# Brakelight2019.net
KiCad netlist of a schematic drawn in EAGLE
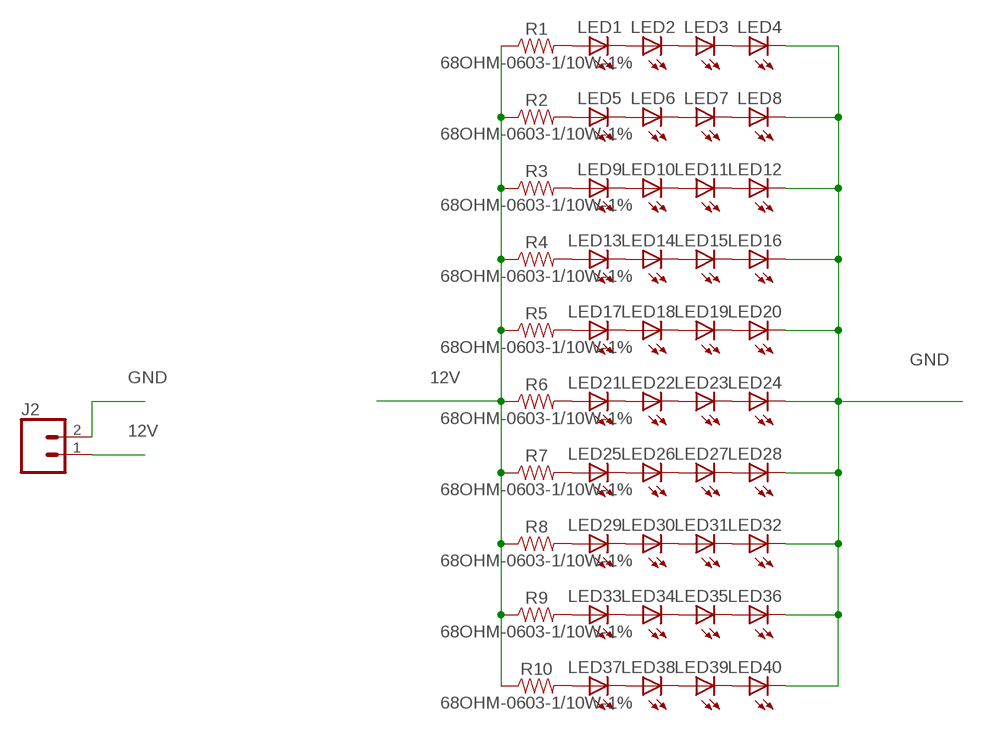
[diagram p0: schematic, sheet 1]

(export (version "E")
  (design (tool "Eeschema 10.0.6"))
  (components
    (comp (ref "J2")
      (value "CONN_02POLAR")
      (footprint "eagle-import:MOLEX-1X2")
      (libsource (lib "eagle-import") (part "CONN_02POLAR"))
    )
    (comp (ref "LED1")
      (value "LED5MM")
      (footprint "eagle-import:LED5MM")
      (libsource (lib "eagle-import") (part "LED5MM"))
    )
    (comp (ref "LED2")
      (value "LED5MM")
      (footprint "eagle-import:LED5MM")
      (libsource (lib "eagle-import") (part "LED5MM"))
    )
    (comp (ref "LED3")
      (value "LED5MM")
      (footprint "eagle-import:LED5MM")
      (libsource (lib "eagle-import") (part "LED5MM"))
    )
    (comp (ref "LED4")
      (value "LED5MM")
      (footprint "eagle-import:LED5MM")
      (libsource (lib "eagle-import") (part "LED5MM"))
    )
    (comp (ref "LED5")
      (value "LED5MM")
      (footprint "eagle-import:LED5MM")
      (libsource (lib "eagle-import") (part "LED5MM"))
    )
    (comp (ref "LED6")
      (value "LED5MM")
      (footprint "eagle-import:LED5MM")
      (libsource (lib "eagle-import") (part "LED5MM"))
    )
    (comp (ref "LED7")
      (value "LED5MM")
      (footprint "eagle-import:LED5MM")
      (libsource (lib "eagle-import") (part "LED5MM"))
    )
    (comp (ref "LED8")
      (value "LED5MM")
      (footprint "eagle-import:LED5MM")
      (libsource (lib "eagle-import") (part "LED5MM"))
    )
    (comp (ref "LED9")
      (value "LED5MM")
      (footprint "eagle-import:LED5MM")
      (libsource (lib "eagle-import") (part "LED5MM"))
    )
    (comp (ref "LED10")
      (value "LED5MM")
      (footprint "eagle-import:LED5MM")
      (libsource (lib "eagle-import") (part "LED5MM"))
    )
    (comp (ref "LED11")
      (value "LED5MM")
      (footprint "eagle-import:LED5MM")
      (libsource (lib "eagle-import") (part "LED5MM"))
    )
    (comp (ref "LED12")
      (value "LED5MM")
      (footprint "eagle-import:LED5MM")
      (libsource (lib "eagle-import") (part "LED5MM"))
    )
    (comp (ref "LED13")
      (value "LED5MM")
      (footprint "eagle-import:LED5MM")
      (libsource (lib "eagle-import") (part "LED5MM"))
    )
    (comp (ref "LED14")
      (value "LED5MM")
      (footprint "eagle-import:LED5MM")
      (libsource (lib "eagle-import") (part "LED5MM"))
    )
    (comp (ref "LED15")
      (value "LED5MM")
      (footprint "eagle-import:LED5MM")
      (libsource (lib "eagle-import") (part "LED5MM"))
    )
    (comp (ref "LED16")
      (value "LED5MM")
      (footprint "eagle-import:LED5MM")
      (libsource (lib "eagle-import") (part "LED5MM"))
    )
    (comp (ref "LED17")
      (value "LED5MM")
      (footprint "eagle-import:LED5MM")
      (libsource (lib "eagle-import") (part "LED5MM"))
    )
    (comp (ref "LED18")
      (value "LED5MM")
      (footprint "eagle-import:LED5MM")
      (libsource (lib "eagle-import") (part "LED5MM"))
    )
    (comp (ref "LED19")
      (value "LED5MM")
      (footprint "eagle-import:LED5MM")
      (libsource (lib "eagle-import") (part "LED5MM"))
    )
    (comp (ref "LED20")
      (value "LED5MM")
      (footprint "eagle-import:LED5MM")
      (libsource (lib "eagle-import") (part "LED5MM"))
    )
    (comp (ref "LED21")
      (value "LED5MM")
      (footprint "eagle-import:LED5MM")
      (libsource (lib "eagle-import") (part "LED5MM"))
    )
    (comp (ref "LED22")
      (value "LED5MM")
      (footprint "eagle-import:LED5MM")
      (libsource (lib "eagle-import") (part "LED5MM"))
    )
    (comp (ref "LED23")
      (value "LED5MM")
      (footprint "eagle-import:LED5MM")
      (libsource (lib "eagle-import") (part "LED5MM"))
    )
    (comp (ref "LED24")
      (value "LED5MM")
      (footprint "eagle-import:LED5MM")
      (libsource (lib "eagle-import") (part "LED5MM"))
    )
    (comp (ref "LED25")
      (value "LED5MM")
      (footprint "eagle-import:LED5MM")
      (libsource (lib "eagle-import") (part "LED5MM"))
    )
    (comp (ref "LED26")
      (value "LED5MM")
      (footprint "eagle-import:LED5MM")
      (libsource (lib "eagle-import") (part "LED5MM"))
    )
    (comp (ref "LED27")
      (value "LED5MM")
      (footprint "eagle-import:LED5MM")
      (libsource (lib "eagle-import") (part "LED5MM"))
    )
    (comp (ref "LED28")
      (value "LED5MM")
      (footprint "eagle-import:LED5MM")
      (libsource (lib "eagle-import") (part "LED5MM"))
    )
    (comp (ref "LED29")
      (value "LED5MM")
      (footprint "eagle-import:LED5MM")
      (libsource (lib "eagle-import") (part "LED5MM"))
    )
    (comp (ref "LED30")
      (value "LED5MM")
      (footprint "eagle-import:LED5MM")
      (libsource (lib "eagle-import") (part "LED5MM"))
    )
    (comp (ref "LED31")
      (value "LED5MM")
      (footprint "eagle-import:LED5MM")
      (libsource (lib "eagle-import") (part "LED5MM"))
    )
    (comp (ref "LED32")
      (value "LED5MM")
      (footprint "eagle-import:LED5MM")
      (libsource (lib "eagle-import") (part "LED5MM"))
    )
    (comp (ref "LED33")
      (value "LED5MM")
      (footprint "eagle-import:LED5MM")
      (libsource (lib "eagle-import") (part "LED5MM"))
    )
    (comp (ref "LED34")
      (value "LED5MM")
      (footprint "eagle-import:LED5MM")
      (libsource (lib "eagle-import") (part "LED5MM"))
    )
    (comp (ref "LED35")
      (value "LED5MM")
      (footprint "eagle-import:LED5MM")
      (libsource (lib "eagle-import") (part "LED5MM"))
    )
    (comp (ref "LED36")
      (value "LED5MM")
      (footprint "eagle-import:LED5MM")
      (libsource (lib "eagle-import") (part "LED5MM"))
    )
    (comp (ref "LED37")
      (value "LED5MM")
      (footprint "eagle-import:LED5MM")
      (libsource (lib "eagle-import") (part "LED5MM"))
    )
    (comp (ref "LED38")
      (value "LED5MM")
      (footprint "eagle-import:LED5MM")
      (libsource (lib "eagle-import") (part "LED5MM"))
    )
    (comp (ref "LED39")
      (value "LED5MM")
      (footprint "eagle-import:LED5MM")
      (libsource (lib "eagle-import") (part "LED5MM"))
    )
    (comp (ref "LED40")
      (value "LED5MM")
      (footprint "eagle-import:LED5MM")
      (libsource (lib "eagle-import") (part "LED5MM"))
    )
    (comp (ref "R1")
      (value "68OHM-0603-1/10W-1%")
      (footprint "eagle-import:0603")
      (libsource (lib "eagle-import") (part "68OHM-0603-1/10W-1%"))
    )
    (comp (ref "R2")
      (value "68OHM-0603-1/10W-1%")
      (footprint "eagle-import:0603")
      (libsource (lib "eagle-import") (part "68OHM-0603-1/10W-1%"))
    )
    (comp (ref "R3")
      (value "68OHM-0603-1/10W-1%")
      (footprint "eagle-import:0603")
      (libsource (lib "eagle-import") (part "68OHM-0603-1/10W-1%"))
    )
    (comp (ref "R4")
      (value "68OHM-0603-1/10W-1%")
      (footprint "eagle-import:0603")
      (libsource (lib "eagle-import") (part "68OHM-0603-1/10W-1%"))
    )
    (comp (ref "R5")
      (value "68OHM-0603-1/10W-1%")
      (footprint "eagle-import:0603")
      (libsource (lib "eagle-import") (part "68OHM-0603-1/10W-1%"))
    )
    (comp (ref "R6")
      (value "68OHM-0603-1/10W-1%")
      (footprint "eagle-import:0603")
      (libsource (lib "eagle-import") (part "68OHM-0603-1/10W-1%"))
    )
    (comp (ref "R7")
      (value "68OHM-0603-1/10W-1%")
      (footprint "eagle-import:0603")
      (libsource (lib "eagle-import") (part "68OHM-0603-1/10W-1%"))
    )
    (comp (ref "R8")
      (value "68OHM-0603-1/10W-1%")
      (footprint "eagle-import:0603")
      (libsource (lib "eagle-import") (part "68OHM-0603-1/10W-1%"))
    )
    (comp (ref "R9")
      (value "68OHM-0603-1/10W-1%")
      (footprint "eagle-import:0603")
      (libsource (lib "eagle-import") (part "68OHM-0603-1/10W-1%"))
    )
    (comp (ref "R10")
      (value "68OHM-0603-1/10W-1%")
      (footprint "eagle-import:0603")
      (libsource (lib "eagle-import") (part "68OHM-0603-1/10W-1%"))
    )
  )
  (nets
    (net (code "1") (name "/12V") (class "Default")
      (node (ref "J2") (pin "1") (pinfunction "1_1") (pintype "passive"))
      (node (ref "R1") (pin "1") (pinfunction "1_1") (pintype "passive"))
      (node (ref "R10") (pin "1") (pinfunction "1_1") (pintype "passive"))
      (node (ref "R2") (pin "1") (pinfunction "1_1") (pintype "passive"))
      (node (ref "R3") (pin "1") (pinfunction "1_1") (pintype "passive"))
      (node (ref "R4") (pin "1") (pinfunction "1_1") (pintype "passive"))
      (node (ref "R5") (pin "1") (pinfunction "1_1") (pintype "passive"))
      (node (ref "R6") (pin "1") (pinfunction "1_1") (pintype "passive"))
      (node (ref "R7") (pin "1") (pinfunction "1_1") (pintype "passive"))
      (node (ref "R8") (pin "1") (pinfunction "1_1") (pintype "passive"))
      (node (ref "R9") (pin "1") (pinfunction "1_1") (pintype "passive"))
    )
    (net (code "2") (name "/GND") (class "Default")
      (node (ref "J2") (pin "2") (pinfunction "2_2") (pintype "passive"))
      (node (ref "LED12") (pin "K") (pinfunction "C_K") (pintype "passive"))
      (node (ref "LED16") (pin "K") (pinfunction "C_K") (pintype "passive"))
      (node (ref "LED20") (pin "K") (pinfunction "C_K") (pintype "passive"))
      (node (ref "LED24") (pin "K") (pinfunction "C_K") (pintype "passive"))
      (node (ref "LED28") (pin "K") (pinfunction "C_K") (pintype "passive"))
      (node (ref "LED32") (pin "K") (pinfunction "C_K") (pintype "passive"))
      (node (ref "LED36") (pin "K") (pinfunction "C_K") (pintype "passive"))
      (node (ref "LED4") (pin "K") (pinfunction "C_K") (pintype "passive"))
      (node (ref "LED40") (pin "K") (pinfunction "C_K") (pintype "passive"))
      (node (ref "LED8") (pin "K") (pinfunction "C_K") (pintype "passive"))
    )
    (net (code "3") (name "Net-(LED1-C)") (class "Default")
      (node (ref "LED1") (pin "K") (pinfunction "C_K") (pintype "passive"))
      (node (ref "LED2") (pin "A") (pinfunction "A_A") (pintype "passive"))
    )
    (net (code "4") (name "Net-(LED1-PadA)") (class "Default")
      (node (ref "LED1") (pin "A") (pinfunction "A_A") (pintype "passive"))
      (node (ref "R1") (pin "2") (pinfunction "2_2") (pintype "passive"))
    )
    (net (code "5") (name "Net-(LED2-C)") (class "Default")
      (node (ref "LED2") (pin "K") (pinfunction "C_K") (pintype "passive"))
      (node (ref "LED3") (pin "A") (pinfunction "A_A") (pintype "passive"))
    )
    (net (code "6") (name "Net-(LED3-C)") (class "Default")
      (node (ref "LED3") (pin "K") (pinfunction "C_K") (pintype "passive"))
      (node (ref "LED4") (pin "A") (pinfunction "A_A") (pintype "passive"))
    )
    (net (code "7") (name "Net-(LED5-C)") (class "Default")
      (node (ref "LED5") (pin "K") (pinfunction "C_K") (pintype "passive"))
      (node (ref "LED6") (pin "A") (pinfunction "A_A") (pintype "passive"))
    )
    (net (code "8") (name "Net-(LED5-PadA)") (class "Default")
      (node (ref "LED5") (pin "A") (pinfunction "A_A") (pintype "passive"))
      (node (ref "R2") (pin "2") (pinfunction "2_2") (pintype "passive"))
    )
    (net (code "9") (name "Net-(LED6-C)") (class "Default")
      (node (ref "LED6") (pin "K") (pinfunction "C_K") (pintype "passive"))
      (node (ref "LED7") (pin "A") (pinfunction "A_A") (pintype "passive"))
    )
    (net (code "10") (name "Net-(LED7-C)") (class "Default")
      (node (ref "LED7") (pin "K") (pinfunction "C_K") (pintype "passive"))
      (node (ref "LED8") (pin "A") (pinfunction "A_A") (pintype "passive"))
    )
    (net (code "11") (name "Net-(LED9-C)") (class "Default")
      (node (ref "LED10") (pin "A") (pinfunction "A_A") (pintype "passive"))
      (node (ref "LED9") (pin "K") (pinfunction "C_K") (pintype "passive"))
    )
    (net (code "12") (name "Net-(LED9-PadA)") (class "Default")
      (node (ref "LED9") (pin "A") (pinfunction "A_A") (pintype "passive"))
      (node (ref "R3") (pin "2") (pinfunction "2_2") (pintype "passive"))
    )
    (net (code "13") (name "Net-(LED10-C)") (class "Default")
      (node (ref "LED10") (pin "K") (pinfunction "C_K") (pintype "passive"))
      (node (ref "LED11") (pin "A") (pinfunction "A_A") (pintype "passive"))
    )
    (net (code "14") (name "Net-(LED11-C)") (class "Default")
      (node (ref "LED11") (pin "K") (pinfunction "C_K") (pintype "passive"))
      (node (ref "LED12") (pin "A") (pinfunction "A_A") (pintype "passive"))
    )
    (net (code "15") (name "Net-(LED13-C)") (class "Default")
      (node (ref "LED13") (pin "K") (pinfunction "C_K") (pintype "passive"))
      (node (ref "LED14") (pin "A") (pinfunction "A_A") (pintype "passive"))
    )
    (net (code "16") (name "Net-(LED13-PadA)") (class "Default")
      (node (ref "LED13") (pin "A") (pinfunction "A_A") (pintype "passive"))
      (node (ref "R4") (pin "2") (pinfunction "2_2") (pintype "passive"))
    )
    (net (code "17") (name "Net-(LED14-C)") (class "Default")
      (node (ref "LED14") (pin "K") (pinfunction "C_K") (pintype "passive"))
      (node (ref "LED15") (pin "A") (pinfunction "A_A") (pintype "passive"))
    )
    (net (code "18") (name "Net-(LED15-C)") (class "Default")
      (node (ref "LED15") (pin "K") (pinfunction "C_K") (pintype "passive"))
      (node (ref "LED16") (pin "A") (pinfunction "A_A") (pintype "passive"))
    )
    (net (code "19") (name "Net-(LED17-C)") (class "Default")
      (node (ref "LED17") (pin "K") (pinfunction "C_K") (pintype "passive"))
      (node (ref "LED18") (pin "A") (pinfunction "A_A") (pintype "passive"))
    )
    (net (code "20") (name "Net-(LED17-PadA)") (class "Default")
      (node (ref "LED17") (pin "A") (pinfunction "A_A") (pintype "passive"))
      (node (ref "R5") (pin "2") (pinfunction "2_2") (pintype "passive"))
    )
    (net (code "21") (name "Net-(LED18-C)") (class "Default")
      (node (ref "LED18") (pin "K") (pinfunction "C_K") (pintype "passive"))
      (node (ref "LED19") (pin "A") (pinfunction "A_A") (pintype "passive"))
    )
    (net (code "22") (name "Net-(LED19-C)") (class "Default")
      (node (ref "LED19") (pin "K") (pinfunction "C_K") (pintype "passive"))
      (node (ref "LED20") (pin "A") (pinfunction "A_A") (pintype "passive"))
    )
    (net (code "23") (name "Net-(LED21-C)") (class "Default")
      (node (ref "LED21") (pin "K") (pinfunction "C_K") (pintype "passive"))
      (node (ref "LED22") (pin "A") (pinfunction "A_A") (pintype "passive"))
    )
    (net (code "24") (name "Net-(LED21-PadA)") (class "Default")
      (node (ref "LED21") (pin "A") (pinfunction "A_A") (pintype "passive"))
      (node (ref "R6") (pin "2") (pinfunction "2_2") (pintype "passive"))
    )
    (net (code "25") (name "Net-(LED22-C)") (class "Default")
      (node (ref "LED22") (pin "K") (pinfunction "C_K") (pintype "passive"))
      (node (ref "LED23") (pin "A") (pinfunction "A_A") (pintype "passive"))
    )
    (net (code "26") (name "Net-(LED23-C)") (class "Default")
      (node (ref "LED23") (pin "K") (pinfunction "C_K") (pintype "passive"))
      (node (ref "LED24") (pin "A") (pinfunction "A_A") (pintype "passive"))
    )
    (net (code "27") (name "Net-(LED25-C)") (class "Default")
      (node (ref "LED25") (pin "K") (pinfunction "C_K") (pintype "passive"))
      (node (ref "LED26") (pin "A") (pinfunction "A_A") (pintype "passive"))
    )
    (net (code "28") (name "Net-(LED25-PadA)") (class "Default")
      (node (ref "LED25") (pin "A") (pinfunction "A_A") (pintype "passive"))
      (node (ref "R7") (pin "2") (pinfunction "2_2") (pintype "passive"))
    )
    (net (code "29") (name "Net-(LED26-C)") (class "Default")
      (node (ref "LED26") (pin "K") (pinfunction "C_K") (pintype "passive"))
      (node (ref "LED27") (pin "A") (pinfunction "A_A") (pintype "passive"))
    )
    (net (code "30") (name "Net-(LED27-C)") (class "Default")
      (node (ref "LED27") (pin "K") (pinfunction "C_K") (pintype "passive"))
      (node (ref "LED28") (pin "A") (pinfunction "A_A") (pintype "passive"))
    )
    (net (code "31") (name "Net-(LED29-C)") (class "Default")
      (node (ref "LED29") (pin "K") (pinfunction "C_K") (pintype "passive"))
      (node (ref "LED30") (pin "A") (pinfunction "A_A") (pintype "passive"))
    )
    (net (code "32") (name "Net-(LED29-PadA)") (class "Default")
      (node (ref "LED29") (pin "A") (pinfunction "A_A") (pintype "passive"))
      (node (ref "R8") (pin "2") (pinfunction "2_2") (pintype "passive"))
    )
    (net (code "33") (name "Net-(LED30-C)") (class "Default")
      (node (ref "LED30") (pin "K") (pinfunction "C_K") (pintype "passive"))
      (node (ref "LED31") (pin "A") (pinfunction "A_A") (pintype "passive"))
    )
    (net (code "34") (name "Net-(LED31-C)") (class "Default")
      (node (ref "LED31") (pin "K") (pinfunction "C_K") (pintype "passive"))
      (node (ref "LED32") (pin "A") (pinfunction "A_A") (pintype "passive"))
    )
    (net (code "35") (name "Net-(LED33-C)") (class "Default")
      (node (ref "LED33") (pin "K") (pinfunction "C_K") (pintype "passive"))
      (node (ref "LED34") (pin "A") (pinfunction "A_A") (pintype "passive"))
    )
    (net (code "36") (name "Net-(LED33-PadA)") (class "Default")
      (node (ref "LED33") (pin "A") (pinfunction "A_A") (pintype "passive"))
      (node (ref "R9") (pin "2") (pinfunction "2_2") (pintype "passive"))
    )
    (net (code "37") (name "Net-(LED34-C)") (class "Default")
      (node (ref "LED34") (pin "K") (pinfunction "C_K") (pintype "passive"))
      (node (ref "LED35") (pin "A") (pinfunction "A_A") (pintype "passive"))
    )
    (net (code "38") (name "Net-(LED35-C)") (class "Default")
      (node (ref "LED35") (pin "K") (pinfunction "C_K") (pintype "passive"))
      (node (ref "LED36") (pin "A") (pinfunction "A_A") (pintype "passive"))
    )
    (net (code "39") (name "Net-(LED37-C)") (class "Default")
      (node (ref "LED37") (pin "K") (pinfunction "C_K") (pintype "passive"))
      (node (ref "LED38") (pin "A") (pinfunction "A_A") (pintype "passive"))
    )
    (net (code "40") (name "Net-(LED37-PadA)") (class "Default")
      (node (ref "LED37") (pin "A") (pinfunction "A_A") (pintype "passive"))
      (node (ref "R10") (pin "2") (pinfunction "2_2") (pintype "passive"))
    )
    (net (code "41") (name "Net-(LED38-C)") (class "Default")
      (node (ref "LED38") (pin "K") (pinfunction "C_K") (pintype "passive"))
      (node (ref "LED39") (pin "A") (pinfunction "A_A") (pintype "passive"))
    )
    (net (code "42") (name "Net-(LED39-C)") (class "Default")
      (node (ref "LED39") (pin "K") (pinfunction "C_K") (pintype "passive"))
      (node (ref "LED40") (pin "A") (pinfunction "A_A") (pintype "passive"))
    )
  )
)
